# Communications.net
KiCad netlist of a schematic drawn in Altium Designer
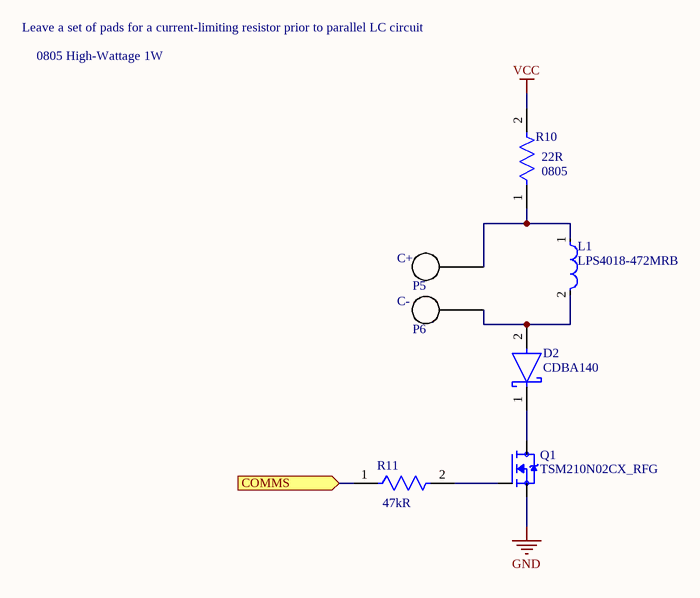
[diagram p0: Communications.SchDoc]

(export (version "E")
  (design (tool "Eeschema 10.0.6"))
  (components
    (comp (ref "D2")
      (value "CDBA140")
      (footprint "FP-95400-MFG")
      (description "DIODE SCHOTTKY 100V 1A SMA")
      (fields
        (field (name "OCTOPART") "https://octopart.com/vs-10mq100ntrpbf-vishay-44340924")
        (field (name "MANUFACTURER") "Vishay")
      )
      (libsource (lib "Altium Content Vault") (part "c1678fac7984e62e0809fbf79c06691"))
    )
    (comp (ref "L1")
      (value "LPS4018-472MRB")
      (footprint "FP-LPS4018-MFG")
      (description "Power inductor, shielded, 20/30% tol, SMT, RoHS, lead-free, halogen-free")
      (fields (field (name "TOLERANCE") "20%") (field (name "MANUFACTURER PART NUMBER") "LPS4018-223MRB"))
      (libsource (lib "Altium Content Vault") (part "725321dda6339637d4d059423bc1c3c"))
    )
    (comp (ref "P5")
      (value "C+")
      (footprint "BlankPad:BlankPad")
      (libsource (lib "BlankPad") (part "BlankPad"))
    )
    (comp (ref "P6")
      (value "C-")
      (footprint "BlankPad:BlankPad")
      (libsource (lib "BlankPad") (part "BlankPad"))
    )
    (comp (ref "Q1")
      (value "TSM210N02CX_RFG")
      (footprint "TRANS_TSM210N02CX_RFG")
      (description "N-Channel 20 V 6.7A (Tc) 1.56W (Tc) Surface Mount SOT-23")
      (fields (field (name "MF") "Taiwan Semiconductor Corporation") (field (name "MP") "TSM210N02CX RFG"))
      (libsource (lib "TSM210N02CX_RFG") (part "TSM210N02CX_RFG"))
    )
    (comp (ref "R10")
      (value "CRCW080522R0FKEA")
      (footprint "FP-CRCW0805-e3-IPC_C")
      (description "RES Thick Film, 22Ω, 1%, 0.125W, 100ppm/°C, 0805")
      (fields
        (field (name "CASE/PACKAGE") "0805")
        (field (name "RESISTANCE") "22R")
        (field (name "TOLERANCE") "1%")
      )
      (libsource (lib "Altium Content Vault") (part "1029c3af85768c4190bb7ad29bc67b5"))
    )
    (comp (ref "R11")
      (value "CRCW080547K0FKEA")
      (footprint "FP-CRCW0805-e3-MFG")
      (description "RES Thick Film, 47kΩ, 1%, 0.125W, 100ppm/°C, 0805")
      (fields (field (name "RESISTANCE") "47kR") (field (name "TOLERANCE") "1%"))
      (libsource (lib "Altium Content Vault") (part "1029c3af85768c4190bb7ad29bc67b5"))
    )
  )
  (nets
    (net (code "1") (name "/COMMS") (class "Default")
      (node (ref "R11") (pin "1") (pinfunction "1_1") (pintype "passive"))
    )
    (net (code "2") (name "GND") (class "Default")
      (node (ref "Q1") (pin "2") (pinfunction "S_2") (pintype "passive"))
    )
    (net (code "3") (name "Net-(D2-A)") (class "Default")
      (node (ref "D2") (pin "2") (pinfunction "A_2") (pintype "passive"))
      (node (ref "L1") (pin "2") (pinfunction "2_2") (pintype "passive"))
    )
    (net (code "4") (name "Net-(D2-C)") (class "Default")
      (node (ref "D2") (pin "1") (pinfunction "C_1") (pintype "passive"))
      (node (ref "Q1") (pin "3") (pinfunction "D_3") (pintype "passive"))
    )
    (net (code "5") (name "Net-(L1-Pad1)") (class "Default")
      (node (ref "L1") (pin "1") (pinfunction "1_1") (pintype "passive"))
      (node (ref "R10") (pin "1") (pinfunction "1_1") (pintype "passive"))
    )
    (net (code "6") (name "Net-(Q1-G)") (class "Default")
      (node (ref "Q1") (pin "1") (pinfunction "G_1") (pintype "passive"))
      (node (ref "R11") (pin "2") (pinfunction "2_2") (pintype "passive"))
    )
    (net (code "7") (name "VCC") (class "Default")
      (node (ref "R10") (pin "2") (pinfunction "2_2") (pintype "passive"))
    )
    (net (code "8") (name "unconnected-(P5-Pad0)") (class "Default")
      (node (ref "P5") (pin "0") (pinfunction "0_0") (pintype "passive"))
    )
    (net (code "9") (name "unconnected-(P6-Pad0)") (class "Default")
      (node (ref "P6") (pin "0") (pinfunction "0_0") (pintype "passive"))
    )
  )
)
